# IB_V2_MCU.net
KiCad netlist of a schematic drawn in Altium Designer
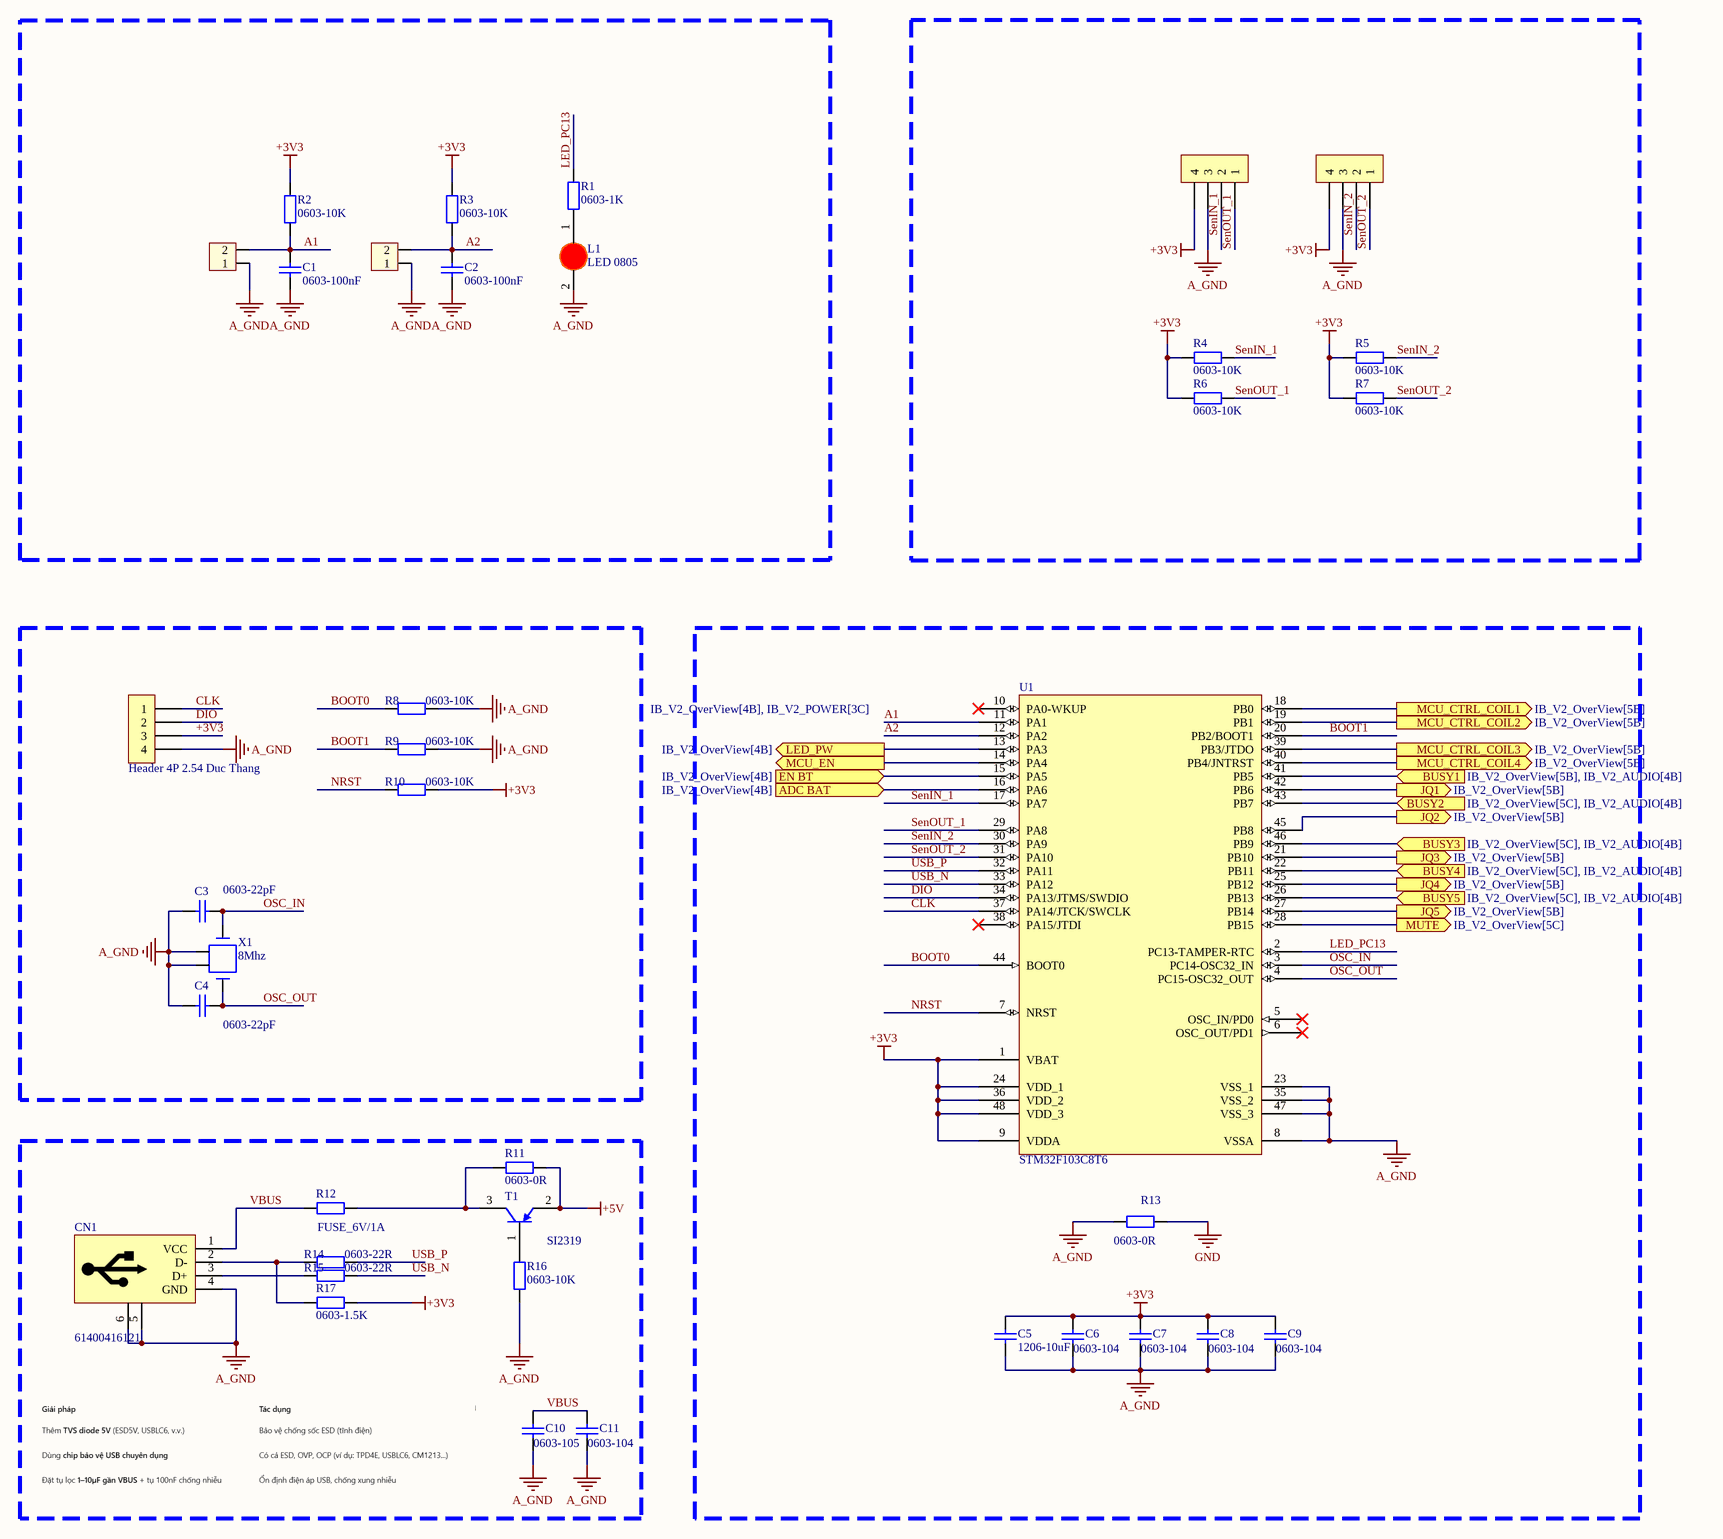
[diagram p0: IB_V2_MCU.SchDoc]

(export (version "E")
  (design (tool "Eeschema 10.0.6"))
  (components
    (comp (ref "C1")
      (value "0603-100nF")
      (footprint "Cap 0603")
      (description "50V 100nF X7R ±5% 0603 Multilayer Ceramic Capacitors MLCC - SMD/SMT ROHS")
      (libsource (lib "thuvien_cty") (part "Cap 0603 100nF"))
    )
    (comp (ref "C2")
      (value "0603-100nF")
      (footprint "Cap 0603")
      (description "50V 100nF X7R ±5% 0603 Multilayer Ceramic Capacitors MLCC - SMD/SMT ROHS")
      (libsource (lib "thuvien_cty") (part "Cap 0603 100nF"))
    )
    (comp (ref "C3")
      (value "0603-22pF")
      (footprint "Cap 0603")
      (description "50V 22pF C0G ±5% 0603 Multilayer Ceramic Capacitors MLCC - SMD/SMT ROHS")
      (libsource (lib "thuvien_cty") (part "Cap 0603 22pF"))
    )
    (comp (ref "C4")
      (value "0603-22pF")
      (footprint "Cap 0603")
      (description "50V 22pF C0G ±5% 0603 Multilayer Ceramic Capacitors MLCC - SMD/SMT ROHS")
      (libsource (lib "thuvien_cty") (part "Cap 0603 22pF"))
    )
    (comp (ref "C5")
      (value "1206-10uF")
      (footprint "Cap 1206")
      (description "50V 10uF X5R ±10% 1206 Multilayer Ceramic Capacitors MLCC - SMD/SMT ROHS")
      (libsource (lib "thuvien_cty") (part "Cap 1206 10uF"))
    )
    (comp (ref "C6")
      (value "0603-104")
      (footprint "Cap 0603")
      (description "50V 100nF X7R ±5% 0603 Multilayer Ceramic Capacitors MLCC - SMD/SMT ROHS")
      (libsource (lib "thuvien_cty") (part "Cap 0603 100nF"))
    )
    (comp (ref "C7")
      (value "0603-104")
      (footprint "Cap 0603")
      (description "50V 100nF X7R ±5% 0603 Multilayer Ceramic Capacitors MLCC - SMD/SMT ROHS")
      (libsource (lib "thuvien_cty") (part "Cap 0603 100nF"))
    )
    (comp (ref "C8")
      (value "0603-104")
      (footprint "Cap 0603")
      (description "50V 100nF X7R ±5% 0603 Multilayer Ceramic Capacitors MLCC - SMD/SMT ROHS")
      (libsource (lib "thuvien_cty") (part "Cap 0603 100nF"))
    )
    (comp (ref "C9")
      (value "0603-104")
      (footprint "Cap 0603")
      (description "50V 100nF X7R ±5% 0603 Multilayer Ceramic Capacitors MLCC - SMD/SMT ROHS")
      (libsource (lib "thuvien_cty") (part "Cap 0603 100nF"))
    )
    (comp (ref "C10")
      (value "0603-105")
      (footprint "Cap 0603")
      (description "50V 100nF X7R ±5% 0603 Multilayer Ceramic Capacitors MLCC - SMD/SMT ROHS")
      (libsource (lib "thuvien_cty") (part "Cap 0603 100nF"))
    )
    (comp (ref "C11")
      (value "0603-104")
      (footprint "Cap 0603")
      (description "50V 100nF X7R ±5% 0603 Multilayer Ceramic Capacitors MLCC - SMD/SMT ROHS")
      (libsource (lib "thuvien_cty") (part "Cap 0603 100nF"))
    )
    (comp (ref "CN1")
      (value "61400416121")
      (footprint "USB-B_61400416121")
      (description "CONN COM TYPE B USB HORZ 4POS")
      (fields (field (name "MANUFACTURER") "Wurth Electronics Inc."))
      (libsource (lib "Indruino") (part "USB_61400416121"))
    )
    (comp (ref "H1")
      (value "Header 4P 2.54 Duc Thang")
      (footprint "XH2.54M-4")
      (description "Cắm")
      (libsource (lib "Altium_Lib_by_KhueNguyenCreator") (part "Header 4P 2.54 Duc Thang"))
    )
    (comp (ref "H2")
      (value "Header 4P 2.54 Duc Thang")
      (footprint "XH2.54M-4")
      (description "Cắm")
      (libsource (lib "Altium_Lib_by_KhueNguyenCreator") (part "Header 4P 2.54 Duc Thang"))
    )
    (comp (ref "H3")
      (value "Header 2P 2.54 Duc Thang")
      (footprint "XH2.54M-2")
      (description "Cắm")
      (libsource (lib "Altium_Lib_by_KhueNguyenCreator") (part "Header 2P 2.54 Duc Thang"))
    )
    (comp (ref "H4")
      (value "Header 2P 2.54 Duc Thang")
      (footprint "XH2.54M-2")
      (description "Cắm")
      (libsource (lib "Altium_Lib_by_KhueNguyenCreator") (part "Header 2P 2.54 Duc Thang"))
    )
    (comp (ref "H5")
      (value "Header 4P 2.54 Duc Thang")
      (footprint "XH2.54M-4")
      (description "Cắm")
      (libsource (lib "") (part "Header 4P 2.54 Duc Thang_1"))
    )
    (comp (ref "L1")
      (value "LED 0805")
      (footprint "LED-0805-Red")
      (description "Dán")
      (libsource (lib "Altium_Lib_by_KhueNguyenCreator") (part "LED 0805 Do"))
    )
    (comp (ref "R1")
      (value "0603-1K")
      (footprint "RES 0603")
      (description "0.1W Thick Film Resistors 75V ±100ppm/℃ ±1% 10kΩ 0603 Chip Resistor - Surface Mount ROHS")
      (libsource (lib "thuvien_cty") (part "Res 0603 10K"))
    )
    (comp (ref "R2")
      (value "0603-10K")
      (footprint "RES 0603")
      (description "0.1W Thick Film Resistors 75V ±100ppm/℃ ±1% 10kΩ 0603 Chip Resistor - Surface Mount ROHS")
      (libsource (lib "thuvien_cty") (part "Res 0603 10K"))
    )
    (comp (ref "R3")
      (value "0603-10K")
      (footprint "RES 0603")
      (description "0.1W Thick Film Resistors 75V ±100ppm/℃ ±1% 10kΩ 0603 Chip Resistor - Surface Mount ROHS")
      (libsource (lib "thuvien_cty") (part "Res 0603 10K"))
    )
    (comp (ref "R4")
      (value "0603-10K")
      (footprint "RES 0603")
      (description "0.1W Thick Film Resistors 75V ±100ppm/℃ ±1% 10kΩ 0603 Chip Resistor - Surface Mount ROHS")
      (libsource (lib "thuvien_cty") (part "Res 0603 10K"))
    )
    (comp (ref "R5")
      (value "0603-10K")
      (footprint "RES 0603")
      (description "0.1W Thick Film Resistors 75V ±100ppm/℃ ±1% 10kΩ 0603 Chip Resistor - Surface Mount ROHS")
      (libsource (lib "thuvien_cty") (part "Res 0603 10K"))
    )
    (comp (ref "R6")
      (value "0603-10K")
      (footprint "RES 0603")
      (description "0.1W Thick Film Resistors 75V ±100ppm/℃ ±1% 10kΩ 0603 Chip Resistor - Surface Mount ROHS")
      (libsource (lib "thuvien_cty") (part "Res 0603 10K"))
    )
    (comp (ref "R7")
      (value "0603-10K")
      (footprint "RES 0603")
      (description "0.1W Thick Film Resistors 75V ±100ppm/℃ ±1% 10kΩ 0603 Chip Resistor - Surface Mount ROHS")
      (libsource (lib "thuvien_cty") (part "Res 0603 10K"))
    )
    (comp (ref "R8")
      (value "0603-10K")
      (footprint "RES 0603")
      (description "100mW Thick Film Resistors 75V ±100ppm/℃ ±1% 22Ω 0603 Chip Resistor - Surface Mount ROHS")
      (libsource (lib "thuvien_cty") (part "Res 0603 22R"))
    )
    (comp (ref "R9")
      (value "0603-10K")
      (footprint "RES 0603")
      (description "100mW Thick Film Resistors 75V ±100ppm/℃ ±1% 22Ω 0603 Chip Resistor - Surface Mount ROHS")
      (libsource (lib "thuvien_cty") (part "Res 0603 22R"))
    )
    (comp (ref "R10")
      (value "0603-10K")
      (footprint "RES 0603")
      (description "100mW Thick Film Resistors 75V ±100ppm/℃ ±1% 22Ω 0603 Chip Resistor - Surface Mount ROHS")
      (libsource (lib "thuvien_cty") (part "Res 0603 22R"))
    )
    (comp (ref "R11")
      (value "0603-0R")
      (footprint "RES 0603")
      (description "100mW Thick Film Resistors 75V ±100ppm/℃ ±1% 22Ω 0603 Chip Resistor - Surface Mount ROHS")
      (libsource (lib "thuvien_cty") (part "Res 0603 22R"))
    )
    (comp (ref "R12")
      (value "FUSE_6V/1A")
      (footprint "tro smd 1206")
      (description "Dán")
      (libsource (lib "Altium_Lib_by_KhueNguyenCreator") (part "Tro 1206 1% 1M"))
    )
    (comp (ref "R13")
      (value "0603-0R")
      (footprint "RES 0603")
      (description "100mW Thick Film Resistors 75V ±100ppm/℃ ±1% 22Ω 0603 Chip Resistor - Surface Mount ROHS")
      (libsource (lib "thuvien_cty") (part "Res 0603 22R"))
    )
    (comp (ref "R14")
      (value "0603-22R")
      (footprint "RES 0603")
      (description "100mW Thick Film Resistors 75V ±100ppm/℃ ±1% 22Ω 0603 Chip Resistor - Surface Mount ROHS")
      (libsource (lib "thuvien_cty") (part "Res 0603 22R"))
    )
    (comp (ref "R15")
      (value "0603-22R")
      (footprint "RES 0603")
      (description "100mW Thick Film Resistors 75V ±100ppm/℃ ±1% 22Ω 0603 Chip Resistor - Surface Mount ROHS")
      (libsource (lib "thuvien_cty") (part "Res 0603 22R"))
    )
    (comp (ref "R16")
      (value "0603-10K")
      (footprint "RES 0603")
      (description "100mW Thick Film Resistors 75V ±100ppm/℃ ±1% 22Ω 0603 Chip Resistor - Surface Mount ROHS")
      (libsource (lib "thuvien_cty") (part "Res 0603 22R"))
    )
    (comp (ref "R17")
      (value "0603-1.5K")
      (footprint "RES 0603")
      (description "100mW Thick Film Resistors 75V ±100ppm/℃ ±1% 22Ω 0603 Chip Resistor - Surface Mount ROHS")
      (libsource (lib "thuvien_cty") (part "Res 0603 22R"))
    )
    (comp (ref "T1")
      (value "SI2319")
      (footprint "SOT - 23")
      (description "P-Channel 40-V(D-S) MOSEFET\r\nSOT-23/3 LEAD")
      (libsource (lib "HTD-AK") (part "Transistor - A1015"))
    )
    (comp (ref "U1")
      (value "STM32F103C8T6")
      (footprint "LQFP48_L")
      (description "IC MCU 32BIT 64KB FLASH 48LQFP")
      (fields
        (field (name "MANUFACTURER") "STMicroelectronics")
        (field (name "BASE PART NUMBER") "STM32F103")
      )
      (libsource (lib "Indruino") (part "STM32F103C8T6"))
    )
    (comp (ref "X1")
      (value "8Mhz")
      (footprint "XTAL_SMD5032")
      (description "CRYSTAL 8.0000MHZ 18PF SMD")
      (libsource (lib "Indruino") (part "XTAL_7B-8.000MAAJ-T"))
    )
  )
  (nets
    (net (code "1") (name "+3V3") (class "Default")
      (node (ref "C5") (pin "1") (pinfunction "1_1") (pintype "passive"))
      (node (ref "C6") (pin "1") (pinfunction "1_1") (pintype "passive"))
      (node (ref "C7") (pin "1") (pinfunction "1_1") (pintype "passive"))
      (node (ref "C8") (pin "1") (pinfunction "1_1") (pintype "passive"))
      (node (ref "C9") (pin "1") (pinfunction "1_1") (pintype "passive"))
      (node (ref "H1") (pin "4") (pinfunction "4_4") (pintype "passive"))
      (node (ref "H2") (pin "4") (pinfunction "4_4") (pintype "passive"))
      (node (ref "H5") (pin "3") (pinfunction "3_3") (pintype "passive"))
      (node (ref "R10") (pin "2") (pinfunction "2_2") (pintype "passive"))
      (node (ref "R17") (pin "1") (pinfunction "1_1") (pintype "passive"))
      (node (ref "R2") (pin "2") (pinfunction "2_2") (pintype "passive"))
      (node (ref "R3") (pin "2") (pinfunction "2_2") (pintype "passive"))
      (node (ref "R4") (pin "1") (pinfunction "1_1") (pintype "passive"))
      (node (ref "R5") (pin "1") (pinfunction "1_1") (pintype "passive"))
      (node (ref "R6") (pin "1") (pinfunction "1_1") (pintype "passive"))
      (node (ref "R7") (pin "1") (pinfunction "1_1") (pintype "passive"))
      (node (ref "U1") (pin "1") (pinfunction "VBAT_1") (pintype "power_in"))
      (node (ref "U1") (pin "24") (pinfunction "VDD_1_24") (pintype "power_in"))
      (node (ref "U1") (pin "36") (pinfunction "VDD_2_36") (pintype "power_in"))
      (node (ref "U1") (pin "48") (pinfunction "VDD_3_48") (pintype "power_in"))
      (node (ref "U1") (pin "9") (pinfunction "VDDA_9") (pintype "power_in"))
    )
    (net (code "2") (name "+5V") (class "Default")
      (node (ref "R11") (pin "1") (pinfunction "1_1") (pintype "passive"))
      (node (ref "T1") (pin "2") (pinfunction "E_2") (pintype "passive"))
    )
    (net (code "3") (name "/A1") (class "Default")
      (node (ref "C1") (pin "1") (pinfunction "1_1") (pintype "passive"))
      (node (ref "H3") (pin "2") (pinfunction "2_2") (pintype "passive"))
      (node (ref "R2") (pin "1") (pinfunction "1_1") (pintype "passive"))
      (node (ref "U1") (pin "11") (pinfunction "PA1_11") (pintype "bidirectional"))
    )
    (net (code "4") (name "/A2") (class "Default")
      (node (ref "C2") (pin "1") (pinfunction "1_1") (pintype "passive"))
      (node (ref "H4") (pin "2") (pinfunction "2_2") (pintype "passive"))
      (node (ref "R3") (pin "1") (pinfunction "1_1") (pintype "passive"))
      (node (ref "U1") (pin "12") (pinfunction "PA2_12") (pintype "bidirectional"))
    )
    (net (code "5") (name "/ADC BAT") (class "Default")
      (node (ref "U1") (pin "16") (pinfunction "PA6_16") (pintype "bidirectional"))
    )
    (net (code "6") (name "/BOOT0") (class "Default")
      (node (ref "R8") (pin "1") (pinfunction "1_1") (pintype "passive"))
      (node (ref "U1") (pin "44") (pinfunction "BOOT0_44") (pintype "input"))
    )
    (net (code "7") (name "/BOOT1") (class "Default")
      (node (ref "R9") (pin "1") (pinfunction "1_1") (pintype "passive"))
      (node (ref "U1") (pin "20") (pinfunction "PB2/BOOT1_20") (pintype "bidirectional"))
    )
    (net (code "8") (name "/BUSY1") (class "Default")
      (node (ref "U1") (pin "41") (pinfunction "PB5_41") (pintype "bidirectional"))
    )
    (net (code "9") (name "/BUSY2") (class "Default")
      (node (ref "U1") (pin "43") (pinfunction "PB7_43") (pintype "bidirectional"))
    )
    (net (code "10") (name "/BUSY3") (class "Default")
      (node (ref "U1") (pin "46") (pinfunction "PB9_46") (pintype "bidirectional"))
    )
    (net (code "11") (name "/BUSY4") (class "Default")
      (node (ref "U1") (pin "22") (pinfunction "PB11_22") (pintype "bidirectional"))
    )
    (net (code "12") (name "/BUSY5") (class "Default")
      (node (ref "U1") (pin "26") (pinfunction "PB13_26") (pintype "bidirectional"))
    )
    (net (code "13") (name "/CLK") (class "Default")
      (node (ref "H5") (pin "1") (pinfunction "1_1") (pintype "passive"))
      (node (ref "U1") (pin "37") (pinfunction "PA14/JTCK/SWCLK_37") (pintype "bidirectional"))
    )
    (net (code "14") (name "/DIO") (class "Default")
      (node (ref "H5") (pin "2") (pinfunction "2_2") (pintype "passive"))
      (node (ref "U1") (pin "34") (pinfunction "PA13/JTMS/SWDIO_34") (pintype "bidirectional"))
    )
    (net (code "15") (name "/EN BT") (class "Default")
      (node (ref "U1") (pin "15") (pinfunction "PA5_15") (pintype "bidirectional"))
    )
    (net (code "16") (name "/JQ1") (class "Default")
      (node (ref "U1") (pin "42") (pinfunction "PB6_42") (pintype "bidirectional"))
    )
    (net (code "17") (name "/JQ2") (class "Default")
      (node (ref "U1") (pin "45") (pinfunction "PB8_45") (pintype "bidirectional"))
    )
    (net (code "18") (name "/JQ3") (class "Default")
      (node (ref "U1") (pin "21") (pinfunction "PB10_21") (pintype "bidirectional"))
    )
    (net (code "19") (name "/JQ4") (class "Default")
      (node (ref "U1") (pin "25") (pinfunction "PB12_25") (pintype "bidirectional"))
    )
    (net (code "20") (name "/JQ5") (class "Default")
      (node (ref "U1") (pin "27") (pinfunction "PB14_27") (pintype "bidirectional"))
    )
    (net (code "21") (name "/LED_PC13") (class "Default")
      (node (ref "R1") (pin "2") (pinfunction "2_2") (pintype "passive"))
      (node (ref "U1") (pin "2") (pinfunction "PC13-TAMPER-RTC_2") (pintype "bidirectional"))
    )
    (net (code "22") (name "/LED_PW") (class "Default")
      (node (ref "U1") (pin "13") (pinfunction "PA3_13") (pintype "bidirectional"))
    )
    (net (code "23") (name "/MCU_CTRL_COIL1") (class "Default")
      (node (ref "U1") (pin "18") (pinfunction "PB0_18") (pintype "bidirectional"))
    )
    (net (code "24") (name "/MCU_CTRL_COIL2") (class "Default")
      (node (ref "U1") (pin "19") (pinfunction "PB1_19") (pintype "bidirectional"))
    )
    (net (code "25") (name "/MCU_CTRL_COIL3") (class "Default")
      (node (ref "U1") (pin "39") (pinfunction "PB3/JTDO_39") (pintype "bidirectional"))
    )
    (net (code "26") (name "/MCU_CTRL_COIL4") (class "Default")
      (node (ref "U1") (pin "40") (pinfunction "PB4/JNTRST_40") (pintype "bidirectional"))
    )
    (net (code "27") (name "/MCU_EN") (class "Default")
      (node (ref "U1") (pin "14") (pinfunction "PA4_14") (pintype "bidirectional"))
    )
    (net (code "28") (name "/MUTE") (class "Default")
      (node (ref "U1") (pin "28") (pinfunction "PB15_28") (pintype "bidirectional"))
    )
    (net (code "29") (name "/NRST") (class "Default")
      (node (ref "R10") (pin "1") (pinfunction "1_1") (pintype "passive"))
      (node (ref "U1") (pin "7") (pinfunction "NRST_7") (pintype "bidirectional"))
    )
    (net (code "30") (name "/OSC_IN") (class "Default")
      (node (ref "C3") (pin "2") (pinfunction "2_2") (pintype "passive"))
      (node (ref "U1") (pin "3") (pinfunction "PC14-OSC32_IN_3") (pintype "bidirectional"))
      (node (ref "X1") (pin "1") (pinfunction "OSC1_1") (pintype "passive"))
    )
    (net (code "31") (name "/OSC_OUT") (class "Default")
      (node (ref "C4") (pin "2") (pinfunction "2_2") (pintype "passive"))
      (node (ref "U1") (pin "4") (pinfunction "PC15-OSC32_OUT_4") (pintype "bidirectional"))
      (node (ref "X1") (pin "3") (pinfunction "OSC2_3") (pintype "passive"))
    )
    (net (code "32") (name "/SenIN_1") (class "Default")
      (node (ref "H1") (pin "2") (pinfunction "2_2") (pintype "passive"))
      (node (ref "R4") (pin "2") (pinfunction "2_2") (pintype "passive"))
      (node (ref "U1") (pin "17") (pinfunction "PA7_17") (pintype "bidirectional"))
    )
    (net (code "33") (name "/SenIN_2") (class "Default")
      (node (ref "H2") (pin "2") (pinfunction "2_2") (pintype "passive"))
      (node (ref "R5") (pin "2") (pinfunction "2_2") (pintype "passive"))
      (node (ref "U1") (pin "30") (pinfunction "PA9_30") (pintype "bidirectional"))
    )
    (net (code "34") (name "/SenOUT_1") (class "Default")
      (node (ref "H1") (pin "1") (pinfunction "1_1") (pintype "passive"))
      (node (ref "R6") (pin "2") (pinfunction "2_2") (pintype "passive"))
      (node (ref "U1") (pin "29") (pinfunction "PA8_29") (pintype "bidirectional"))
    )
    (net (code "35") (name "/SenOUT_2") (class "Default")
      (node (ref "H2") (pin "1") (pinfunction "1_1") (pintype "passive"))
      (node (ref "R7") (pin "2") (pinfunction "2_2") (pintype "passive"))
      (node (ref "U1") (pin "31") (pinfunction "PA10_31") (pintype "bidirectional"))
    )
    (net (code "36") (name "/USB_N") (class "Default")
      (node (ref "R15") (pin "2") (pinfunction "2_2") (pintype "passive"))
      (node (ref "U1") (pin "33") (pinfunction "PA12_33") (pintype "bidirectional"))
    )
    (net (code "37") (name "/USB_P") (class "Default")
      (node (ref "R14") (pin "2") (pinfunction "2_2") (pintype "passive"))
      (node (ref "U1") (pin "32") (pinfunction "PA11_32") (pintype "bidirectional"))
    )
    (net (code "38") (name "/VBUS") (class "Default")
      (node (ref "C10") (pin "1") (pinfunction "1_1") (pintype "passive"))
      (node (ref "C11") (pin "1") (pinfunction "1_1") (pintype "passive"))
      (node (ref "CN1") (pin "1") (pinfunction "VCC_1") (pintype "passive"))
      (node (ref "R12") (pin "1") (pinfunction "1_1") (pintype "passive"))
    )
    (net (code "39") (name "A_GND") (class "Default")
      (node (ref "C1") (pin "2") (pinfunction "2_2") (pintype "passive"))
      (node (ref "C10") (pin "2") (pinfunction "2_2") (pintype "passive"))
      (node (ref "C11") (pin "2") (pinfunction "2_2") (pintype "passive"))
      (node (ref "C2") (pin "2") (pinfunction "2_2") (pintype "passive"))
      (node (ref "C3") (pin "1") (pinfunction "1_1") (pintype "passive"))
      (node (ref "C4") (pin "1") (pinfunction "1_1") (pintype "passive"))
      (node (ref "C5") (pin "2") (pinfunction "2_2") (pintype "passive"))
      (node (ref "C6") (pin "2") (pinfunction "2_2") (pintype "passive"))
      (node (ref "C7") (pin "2") (pinfunction "2_2") (pintype "passive"))
      (node (ref "C8") (pin "2") (pinfunction "2_2") (pintype "passive"))
      (node (ref "C9") (pin "2") (pinfunction "2_2") (pintype "passive"))
      (node (ref "CN1") (pin "4") (pinfunction "GND_4") (pintype "passive"))
      (node (ref "CN1") (pin "5") (pinfunction "GND_5") (pintype "passive"))
      (node (ref "CN1") (pin "6") (pinfunction "GND_6") (pintype "power_in"))
      (node (ref "H1") (pin "3") (pinfunction "3_3") (pintype "passive"))
      (node (ref "H2") (pin "3") (pinfunction "3_3") (pintype "passive"))
      (node (ref "H3") (pin "1") (pinfunction "1_1") (pintype "passive"))
      (node (ref "H4") (pin "1") (pinfunction "1_1") (pintype "passive"))
      (node (ref "H5") (pin "4") (pinfunction "4_4") (pintype "passive"))
      (node (ref "L1") (pin "2") (pinfunction "K_2") (pintype "passive"))
      (node (ref "R13") (pin "1") (pinfunction "1_1") (pintype "passive"))
      (node (ref "R16") (pin "2") (pinfunction "2_2") (pintype "passive"))
      (node (ref "R8") (pin "2") (pinfunction "2_2") (pintype "passive"))
      (node (ref "R9") (pin "2") (pinfunction "2_2") (pintype "passive"))
      (node (ref "U1") (pin "23") (pinfunction "VSS_1_23") (pintype "power_in"))
      (node (ref "U1") (pin "35") (pinfunction "VSS_2_35") (pintype "power_in"))
      (node (ref "U1") (pin "47") (pinfunction "VSS_3_47") (pintype "power_in"))
      (node (ref "U1") (pin "8") (pinfunction "VSSA_8") (pintype "power_in"))
      (node (ref "X1") (pin "2") (pinfunction "GND_2") (pintype "passive"))
      (node (ref "X1") (pin "4") (pinfunction "GND_4") (pintype "passive"))
    )
    (net (code "40") (name "GND") (class "Default")
      (node (ref "R13") (pin "2") (pinfunction "2_2") (pintype "passive"))
    )
    (net (code "41") (name "Net-(CN1-D+)") (class "Default")
      (node (ref "CN1") (pin "3") (pinfunction "D+_3") (pintype "passive"))
      (node (ref "R15") (pin "1") (pinfunction "1_1") (pintype "passive"))
    )
    (net (code "42") (name "Net-(CN1-D-)") (class "Default")
      (node (ref "CN1") (pin "2") (pinfunction "D-_2") (pintype "passive"))
      (node (ref "R14") (pin "1") (pinfunction "1_1") (pintype "passive"))
      (node (ref "R17") (pin "2") (pinfunction "2_2") (pintype "passive"))
    )
    (net (code "43") (name "Net-(L1-A)") (class "Default")
      (node (ref "L1") (pin "1") (pinfunction "A_1") (pintype "passive"))
      (node (ref "R1") (pin "1") (pinfunction "1_1") (pintype "passive"))
    )
    (net (code "44") (name "Net-(T1-B)") (class "Default")
      (node (ref "R16") (pin "1") (pinfunction "1_1") (pintype "passive"))
      (node (ref "T1") (pin "1") (pinfunction "B_1") (pintype "passive"))
    )
    (net (code "45") (name "Net-(T1-C)") (class "Default")
      (node (ref "R11") (pin "2") (pinfunction "2_2") (pintype "passive"))
      (node (ref "R12") (pin "2") (pinfunction "2_2") (pintype "passive"))
      (node (ref "T1") (pin "3") (pinfunction "C_3") (pintype "passive"))
    )
    (net (code "46") (name "unconnected-(U1-OSC_IN{slash}PD0-Pad5)") (class "Default")
      (node (ref "U1") (pin "5") (pinfunction "OSC_IN/PD0_5") (pintype "input+no_connect"))
    )
    (net (code "47") (name "unconnected-(U1-OSC_OUT{slash}PD1-Pad6)") (class "Default")
      (node (ref "U1") (pin "6") (pinfunction "OSC_OUT/PD1_6") (pintype "output+no_connect"))
    )
    (net (code "48") (name "unconnected-(U1-PA0-WKUP-Pad10)") (class "Default")
      (node (ref "U1") (pin "10") (pinfunction "PA0-WKUP_10") (pintype "bidirectional+no_connect"))
    )
    (net (code "49") (name "unconnected-(U1-PA15{slash}JTDI-Pad38)") (class "Default")
      (node (ref "U1") (pin "38") (pinfunction "PA15/JTDI_38") (pintype "bidirectional+no_connect"))
    )
  )
)
